# MainBoard.net
KiCad netlist of a schematic drawn in EAGLE
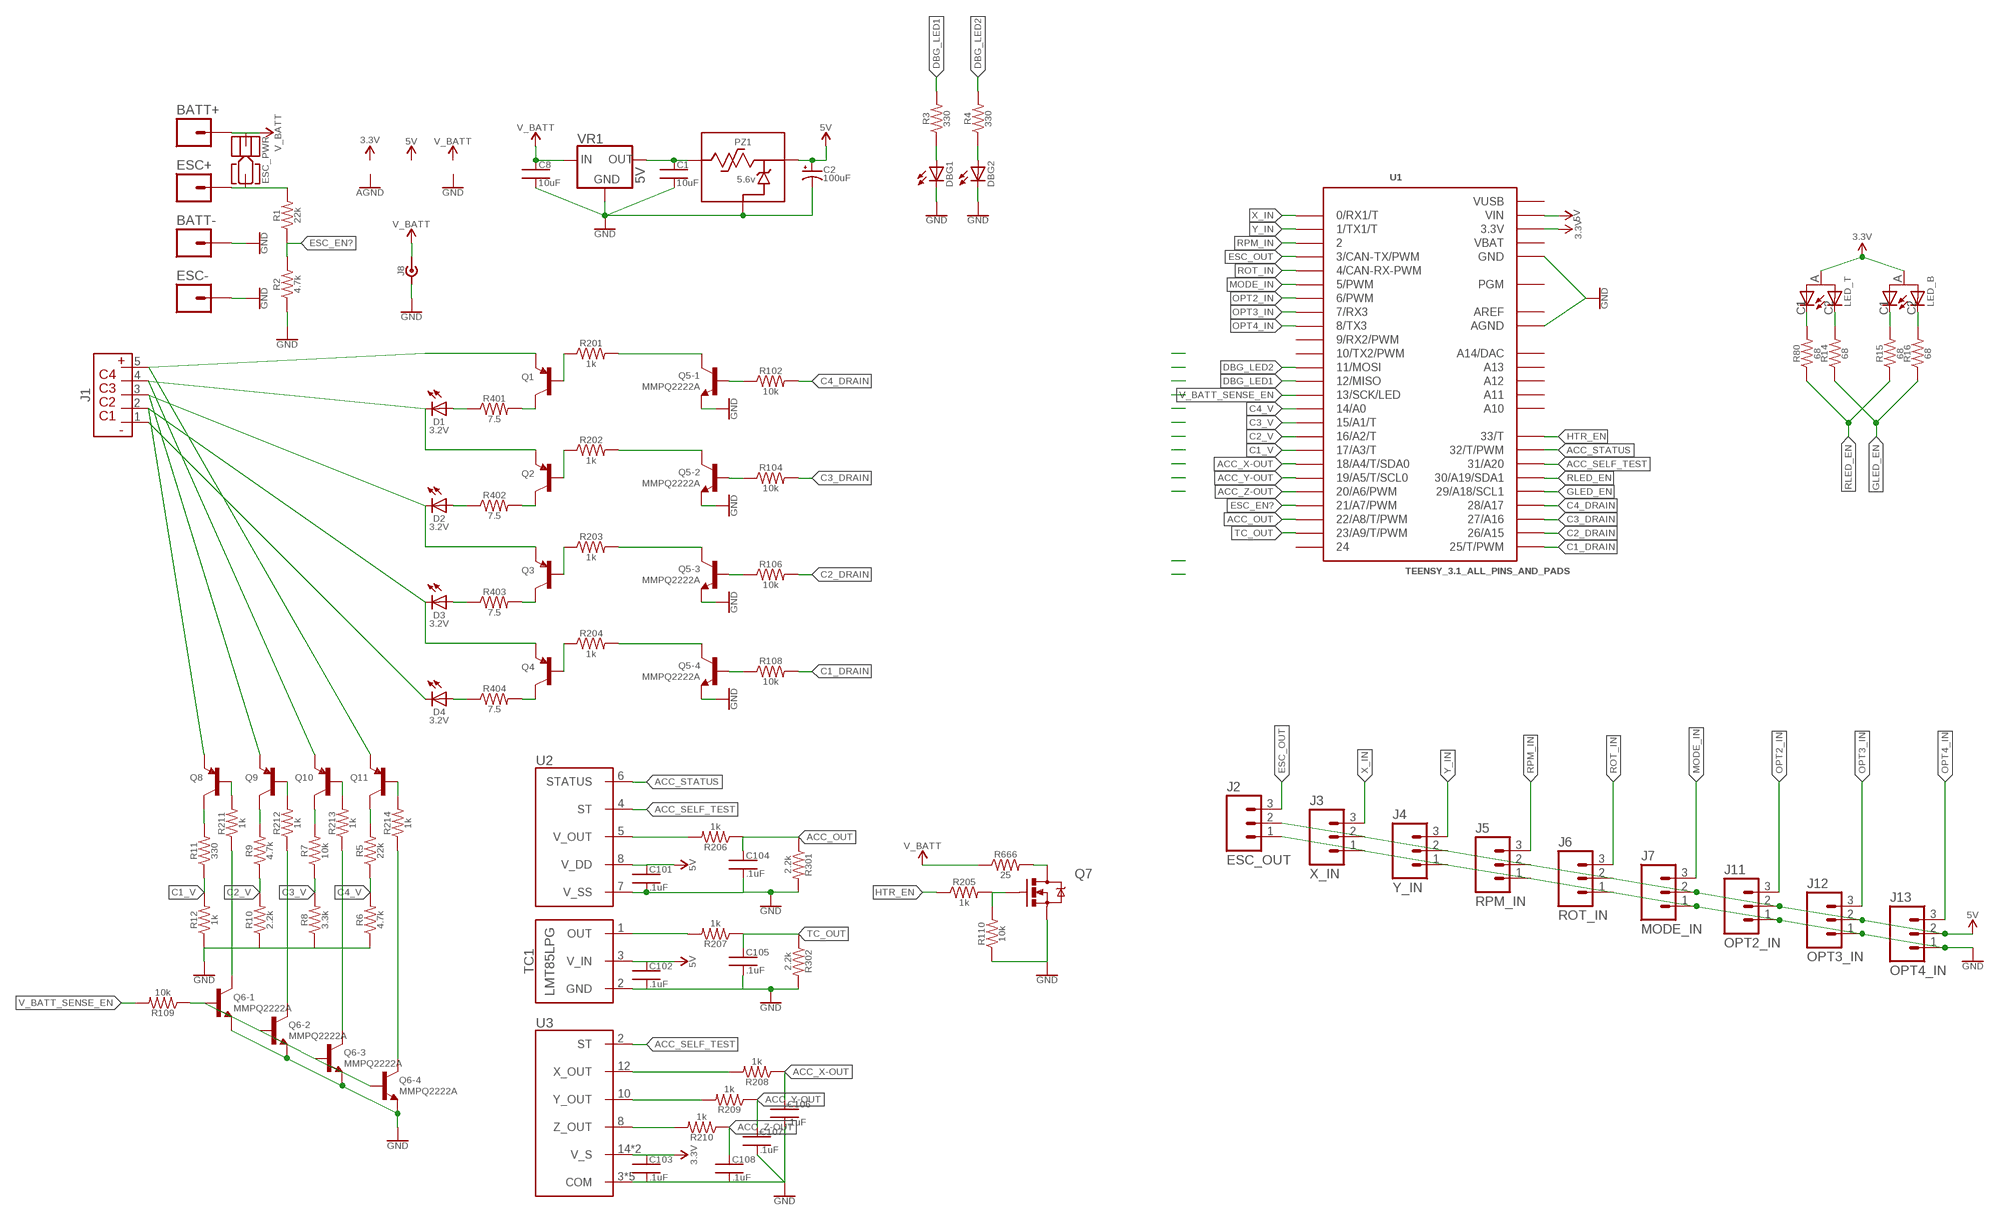
[diagram p0: schematic, sheet 1]

(export (version "E")
  (design (tool "Eeschema 10.0.6"))
  (components
    (comp (ref "BATT+")
      (value "14AWG")
      (footprint "eagle-import:14AWG_SMD")
      (libsource (lib "eagle-import") (part "14AWG"))
    )
    (comp (ref "BATT-")
      (value "14AWG")
      (footprint "eagle-import:14AWG_SMD")
      (libsource (lib "eagle-import") (part "14AWG"))
    )
    (comp (ref "C1")
      (value "10uF")
      (footprint "eagle-import:0805")
      (libsource (lib "eagle-import") (part "CAP_SMD"))
    )
    (comp (ref "C2")
      (value "100uF")
      (footprint "eagle-import:2917_D-CASE")
      (libsource (lib "eagle-import") (part "CAP_POL_SMD"))
    )
    (comp (ref "C8")
      (value "10uF")
      (footprint "eagle-import:0805")
      (libsource (lib "eagle-import") (part "CAP_SMD"))
    )
    (comp (ref "C101")
      (value ".1uF")
      (footprint "eagle-import:0805")
      (libsource (lib "eagle-import") (part "CAP_SMD"))
    )
    (comp (ref "C102")
      (value ".1uF")
      (footprint "eagle-import:0805")
      (libsource (lib "eagle-import") (part "CAP_SMD"))
    )
    (comp (ref "C103")
      (value ".1uF")
      (footprint "eagle-import:0805")
      (libsource (lib "eagle-import") (part "CAP_SMD"))
    )
    (comp (ref "C104")
      (value ".1uF")
      (footprint "eagle-import:0805")
      (libsource (lib "eagle-import") (part "CAP_SMD"))
    )
    (comp (ref "C105")
      (value ".1uF")
      (footprint "eagle-import:0805")
      (libsource (lib "eagle-import") (part "CAP_SMD"))
    )
    (comp (ref "C106")
      (value ".1uF")
      (footprint "eagle-import:0805")
      (libsource (lib "eagle-import") (part "CAP_SMD"))
    )
    (comp (ref "C107")
      (value ".1uF")
      (footprint "eagle-import:0805")
      (libsource (lib "eagle-import") (part "CAP_SMD"))
    )
    (comp (ref "C108")
      (value ".1uF")
      (footprint "eagle-import:0805")
      (libsource (lib "eagle-import") (part "CAP_SMD"))
    )
    (comp (ref "D1")
      (value "3.2V")
      (footprint "eagle-import:LED-2835")
      (libsource (lib "eagle-import") (part "LED2835"))
    )
    (comp (ref "D2")
      (value "3.2V")
      (footprint "eagle-import:LED-2835")
      (libsource (lib "eagle-import") (part "LED2835"))
    )
    (comp (ref "D3")
      (value "3.2V")
      (footprint "eagle-import:LED-2835")
      (libsource (lib "eagle-import") (part "LED2835"))
    )
    (comp (ref "D4")
      (value "3.2V")
      (footprint "eagle-import:LED-2835")
      (libsource (lib "eagle-import") (part "LED2835"))
    )
    (comp (ref "DBG1")
      (value "LED1206")
      (footprint "eagle-import:LED-1206")
      (libsource (lib "eagle-import") (part "LED1206"))
    )
    (comp (ref "DBG2")
      (value "LED1206")
      (footprint "eagle-import:LED-1206")
      (libsource (lib "eagle-import") (part "LED1206"))
    )
    (comp (ref "ESC+")
      (value "14AWG")
      (footprint "eagle-import:14AWG_SMD")
      (libsource (lib "eagle-import") (part "14AWG"))
    )
    (comp (ref "ESC-")
      (value "14AWG")
      (footprint "eagle-import:14AWG_SMD")
      (libsource (lib "eagle-import") (part "14AWG"))
    )
    (comp (ref "ESC_PWR")
      (value "JACK_PWR_SCREW")
      (footprint "eagle-import:JACK_PWR_SCREW")
      (libsource (lib "eagle-import") (part "JACK_PWR_SCREW"))
    )
    (comp (ref "J1")
      (value "BATT_BALANCER_PLUG_4S")
      (footprint "eagle-import:JST_MALE_5_PIN")
      (libsource (lib "eagle-import") (part "BATT_BALANCER_PLUG_4S"))
    )
    (comp (ref "J2")
      (value "ESC_OUT")
      (footprint "eagle-import:1X03")
      (libsource (lib "eagle-import") (part "M03"))
    )
    (comp (ref "J3")
      (value "X_IN")
      (footprint "eagle-import:1X03")
      (libsource (lib "eagle-import") (part "M03"))
    )
    (comp (ref "J4")
      (value "Y_IN")
      (footprint "eagle-import:1X03")
      (libsource (lib "eagle-import") (part "M03"))
    )
    (comp (ref "J5")
      (value "RPM_IN")
      (footprint "eagle-import:1X03")
      (libsource (lib "eagle-import") (part "M03"))
    )
    (comp (ref "J6")
      (value "ROT_IN")
      (footprint "eagle-import:1X03")
      (libsource (lib "eagle-import") (part "M03"))
    )
    (comp (ref "J7")
      (value "MODE_IN")
      (footprint "eagle-import:1X03")
      (libsource (lib "eagle-import") (part "M03"))
    )
    (comp (ref "J8")
      (value "PJ-082BH")
      (footprint "eagle-import:PJ-082BH")
      (libsource (lib "eagle-import") (part "PJ-082BH"))
    )
    (comp (ref "J11")
      (value "OPT2_IN")
      (footprint "eagle-import:1X03")
      (libsource (lib "eagle-import") (part "M03"))
    )
    (comp (ref "J12")
      (value "OPT3_IN")
      (footprint "eagle-import:1X03")
      (libsource (lib "eagle-import") (part "M03"))
    )
    (comp (ref "J13")
      (value "OPT4_IN")
      (footprint "eagle-import:1X03")
      (libsource (lib "eagle-import") (part "M03"))
    )
    (comp (ref "LED_B")
      (value "DIALIGHT_597-2751-607F")
      (footprint "eagle-import:DIALIGHT_1208_BI-COLOR")
      (libsource (lib "eagle-import") (part "DIALIGHT_597-2751-607F"))
    )
    (comp (ref "LED_T")
      (value "DIALIGHT_597-2751-607F")
      (footprint "eagle-import:DIALIGHT_1208_BI-COLOR")
      (libsource (lib "eagle-import") (part "DIALIGHT_597-2751-607F"))
    )
    (comp (ref "PZ1")
      (value "5.6v")
      (footprint "eagle-import:POLYZEN_LS")
      (libsource (lib "eagle-import") (part "POLYZEN_LS"))
    )
    (comp (ref "Q1")
      (value "BJT_PNP")
      (footprint "eagle-import:SOT23-3")
      (libsource (lib "eagle-import") (part "BJT_PNP"))
    )
    (comp (ref "Q2")
      (value "BJT_PNP")
      (footprint "eagle-import:SOT23-3")
      (libsource (lib "eagle-import") (part "BJT_PNP"))
    )
    (comp (ref "Q3")
      (value "BJT_PNP")
      (footprint "eagle-import:SOT23-3")
      (libsource (lib "eagle-import") (part "BJT_PNP"))
    )
    (comp (ref "Q4")
      (value "BJT_PNP")
      (footprint "eagle-import:SOT23-3")
      (libsource (lib "eagle-import") (part "BJT_PNP"))
    )
    (comp (ref "Q5")
      (value "MMPQ2222A")
      (footprint "eagle-import:SOIC_16")
      (libsource (lib "eagle-import") (part "MMPQ2222A"))
    )
    (comp (ref "Q6")
      (value "MMPQ2222A")
      (footprint "eagle-import:SOIC_16")
      (libsource (lib "eagle-import") (part "MMPQ2222A"))
    )
    (comp (ref "Q7")
      (value "MOSFET_N-CHANNEL_SOT23-3")
      (footprint "eagle-import:SOT23-3")
      (libsource (lib "eagle-import") (part "MOSFET_N-CHANNEL_SOT23-3"))
    )
    (comp (ref "Q8")
      (value "BJT_PNP")
      (footprint "eagle-import:SOT23-3")
      (libsource (lib "eagle-import") (part "BJT_PNP"))
    )
    (comp (ref "Q9")
      (value "BJT_PNP")
      (footprint "eagle-import:SOT23-3")
      (libsource (lib "eagle-import") (part "BJT_PNP"))
    )
    (comp (ref "Q10")
      (value "BJT_PNP")
      (footprint "eagle-import:SOT23-3")
      (libsource (lib "eagle-import") (part "BJT_PNP"))
    )
    (comp (ref "Q11")
      (value "BJT_PNP")
      (footprint "eagle-import:SOT23-3")
      (libsource (lib "eagle-import") (part "BJT_PNP"))
    )
    (comp (ref "R1")
      (value "22k")
      (footprint "eagle-import:0805")
      (libsource (lib "eagle-import") (part "RES_SMD0805"))
    )
    (comp (ref "R2")
      (value "4.7k")
      (footprint "eagle-import:0805")
      (libsource (lib "eagle-import") (part "RES_SMD0805"))
    )
    (comp (ref "R3")
      (value "330")
      (footprint "eagle-import:0805")
      (libsource (lib "eagle-import") (part "RES_SMD0805"))
    )
    (comp (ref "R4")
      (value "330")
      (footprint "eagle-import:0805")
      (libsource (lib "eagle-import") (part "RES_SMD0805"))
    )
    (comp (ref "R5")
      (value "22k")
      (footprint "eagle-import:0805")
      (libsource (lib "eagle-import") (part "RES_SMD0805"))
    )
    (comp (ref "R6")
      (value "4.7k")
      (footprint "eagle-import:0805")
      (libsource (lib "eagle-import") (part "RES_SMD0805"))
    )
    (comp (ref "R7")
      (value "10k")
      (footprint "eagle-import:0805")
      (libsource (lib "eagle-import") (part "RES_SMD0805"))
    )
    (comp (ref "R8")
      (value "3.3k")
      (footprint "eagle-import:0805")
      (libsource (lib "eagle-import") (part "RES_SMD0805"))
    )
    (comp (ref "R9")
      (value "4.7k")
      (footprint "eagle-import:0805")
      (libsource (lib "eagle-import") (part "RES_SMD0805"))
    )
    (comp (ref "R10")
      (value "2.2k")
      (footprint "eagle-import:0805")
      (libsource (lib "eagle-import") (part "RES_SMD0805"))
    )
    (comp (ref "R11")
      (value "330")
      (footprint "eagle-import:0805")
      (libsource (lib "eagle-import") (part "RES_SMD0805"))
    )
    (comp (ref "R12")
      (value "1k")
      (footprint "eagle-import:0805")
      (libsource (lib "eagle-import") (part "RES_SMD0805"))
    )
    (comp (ref "R14")
      (value "68")
      (footprint "eagle-import:0805")
      (libsource (lib "eagle-import") (part "RES_SMD0805"))
    )
    (comp (ref "R15")
      (value "68")
      (footprint "eagle-import:0805")
      (libsource (lib "eagle-import") (part "RES_SMD0805"))
    )
    (comp (ref "R16")
      (value "68")
      (footprint "eagle-import:0805")
      (libsource (lib "eagle-import") (part "RES_SMD0805"))
    )
    (comp (ref "R80")
      (value "68")
      (footprint "eagle-import:0805")
      (libsource (lib "eagle-import") (part "RES_SMD0805"))
    )
    (comp (ref "R102")
      (value "10k")
      (footprint "eagle-import:0805")
      (libsource (lib "eagle-import") (part "RES_SMD0805"))
    )
    (comp (ref "R104")
      (value "10k")
      (footprint "eagle-import:0805")
      (libsource (lib "eagle-import") (part "RES_SMD0805"))
    )
    (comp (ref "R106")
      (value "10k")
      (footprint "eagle-import:0805")
      (libsource (lib "eagle-import") (part "RES_SMD0805"))
    )
    (comp (ref "R108")
      (value "10k")
      (footprint "eagle-import:0805")
      (libsource (lib "eagle-import") (part "RES_SMD0805"))
    )
    (comp (ref "R109")
      (value "10k")
      (footprint "eagle-import:0805")
      (libsource (lib "eagle-import") (part "RES_SMD0805"))
    )
    (comp (ref "R110")
      (value "10k")
      (footprint "eagle-import:0805")
      (libsource (lib "eagle-import") (part "RES_SMD0805"))
    )
    (comp (ref "R201")
      (value "1k")
      (footprint "eagle-import:0805")
      (libsource (lib "eagle-import") (part "RES_SMD0805"))
    )
    (comp (ref "R202")
      (value "1k")
      (footprint "eagle-import:0805")
      (libsource (lib "eagle-import") (part "RES_SMD0805"))
    )
    (comp (ref "R203")
      (value "1k")
      (footprint "eagle-import:0805")
      (libsource (lib "eagle-import") (part "RES_SMD0805"))
    )
    (comp (ref "R204")
      (value "1k")
      (footprint "eagle-import:0805")
      (libsource (lib "eagle-import") (part "RES_SMD0805"))
    )
    (comp (ref "R205")
      (value "1k")
      (footprint "eagle-import:0805")
      (libsource (lib "eagle-import") (part "RES_SMD0805"))
    )
    (comp (ref "R206")
      (value "1k")
      (footprint "eagle-import:0805")
      (libsource (lib "eagle-import") (part "RES_SMD0805"))
    )
    (comp (ref "R207")
      (value "1k")
      (footprint "eagle-import:0805")
      (libsource (lib "eagle-import") (part "RES_SMD0805"))
    )
    (comp (ref "R208")
      (value "1k")
      (footprint "eagle-import:0805")
      (libsource (lib "eagle-import") (part "RES_SMD0805"))
    )
    (comp (ref "R209")
      (value "1k")
      (footprint "eagle-import:0805")
      (libsource (lib "eagle-import") (part "RES_SMD0805"))
    )
    (comp (ref "R210")
      (value "1k")
      (footprint "eagle-import:0805")
      (libsource (lib "eagle-import") (part "RES_SMD0805"))
    )
    (comp (ref "R211")
      (value "1k")
      (footprint "eagle-import:0805")
      (libsource (lib "eagle-import") (part "RES_SMD0805"))
    )
    (comp (ref "R212")
      (value "1k")
      (footprint "eagle-import:0805")
      (libsource (lib "eagle-import") (part "RES_SMD0805"))
    )
    (comp (ref "R213")
      (value "1k")
      (footprint "eagle-import:0805")
      (libsource (lib "eagle-import") (part "RES_SMD0805"))
    )
    (comp (ref "R214")
      (value "1k")
      (footprint "eagle-import:0805")
      (libsource (lib "eagle-import") (part "RES_SMD0805"))
    )
    (comp (ref "R301")
      (value "2.2k")
      (footprint "eagle-import:0805")
      (libsource (lib "eagle-import") (part "RES_SMD0805"))
    )
    (comp (ref "R302")
      (value "2.2k")
      (footprint "eagle-import:0805")
      (libsource (lib "eagle-import") (part "RES_SMD0805"))
    )
    (comp (ref "R401")
      (value "7.5")
      (footprint "eagle-import:1206")
      (libsource (lib "eagle-import") (part "RES_SMD1206"))
    )
    (comp (ref "R402")
      (value "7.5")
      (footprint "eagle-import:1206")
      (libsource (lib "eagle-import") (part "RES_SMD1206"))
    )
    (comp (ref "R403")
      (value "7.5")
      (footprint "eagle-import:1206")
      (libsource (lib "eagle-import") (part "RES_SMD1206"))
    )
    (comp (ref "R404")
      (value "7.5")
      (footprint "eagle-import:1206")
      (libsource (lib "eagle-import") (part "RES_SMD1206"))
    )
    (comp (ref "R666")
      (value "25")
      (footprint "eagle-import:TO-220-R")
      (libsource (lib "eagle-import") (part "AP851"))
    )
    (comp (ref "TC1")
      (value "LMT85LPG")
      (footprint "eagle-import:TO-92")
      (libsource (lib "eagle-import") (part "LMT85LPG"))
    )
    (comp (ref "U1")
      (value "TEENSY_3.1_ALL_PINS_AND_PADS")
      (footprint "eagle-import:TEENSY_3.1_ALLPINS")
      (libsource (lib "eagle-import") (part "TEENSY_3.1_ALL_PINS_AND_PADS"))
    )
    (comp (ref "U2")
      (value "MMA1211KEG")
      (footprint "eagle-import:SOIC_16_WIDE")
      (libsource (lib "eagle-import") (part "MMA1211KEG"))
    )
    (comp (ref "U3")
      (value "ADXL326")
      (footprint "eagle-import:LFCSP_LQ")
      (libsource (lib "eagle-import") (part "ADXL326"))
    )
    (comp (ref "VR1")
      (value "5V")
      (footprint "eagle-import:TSR_2-XXXX")
      (libsource (lib "eagle-import") (part "TSR_2-XXXX"))
    )
  )
  (nets
    (net (code "1") (name "/AREF") (class "Default")
      (node (ref "U1") (pin "AREF") (pinfunction "AREF_AREF") (pintype "power_in"))
    )
    (net (code "2") (name "/VBAT") (class "Default")
      (node (ref "U1") (pin "VBAT") (pinfunction "VBAT_VBAT") (pintype "power_in"))
    )
    (net (code "3") (name "/VUSB") (class "Default")
      (node (ref "U1") (pin "VUSB") (pinfunction "VUSB_VUSB") (pintype "power_in"))
    )
    (net (code "4") (name "3.3V") (class "Default")
      (node (ref "C103") (pin "1") (pinfunction "1_1") (pintype "passive"))
      (node (ref "LED_B") (pin "A") (pinfunction "A_A") (pintype "passive"))
      (node (ref "LED_T") (pin "A") (pinfunction "A_A") (pintype "passive"))
      (node (ref "U1") (pin "3.3V") (pinfunction "3.3V_3.3V") (pintype "power_in"))
      (node (ref "U1") (pin "3.3V1") (pinfunction "3.3V_3.3V1") (pintype "power_in"))
      (node (ref "U1") (pin "3.3V2") (pinfunction "3.3V_3.3V2") (pintype "power_in"))
      (node (ref "U3") (pin "14") (pinfunction "V_S_14") (pintype "bidirectional"))
      (node (ref "U3") (pin "15") (pinfunction "V_S_15") (pintype "bidirectional"))
    )
    (net (code "5") (name "5V") (class "Default")
      (node (ref "C101") (pin "1") (pinfunction "1_1") (pintype "passive"))
      (node (ref "C102") (pin "1") (pinfunction "1_1") (pintype "passive"))
      (node (ref "C2") (pin "A+") (pinfunction "+_A+") (pintype "passive"))
      (node (ref "J11") (pin "2") (pinfunction "2_2") (pintype "passive"))
      (node (ref "J12") (pin "2") (pinfunction "2_2") (pintype "passive"))
      (node (ref "J13") (pin "2") (pinfunction "2_2") (pintype "passive"))
      (node (ref "J2") (pin "2") (pinfunction "2_2") (pintype "passive"))
      (node (ref "J3") (pin "2") (pinfunction "2_2") (pintype "passive"))
      (node (ref "J4") (pin "2") (pinfunction "2_2") (pintype "passive"))
      (node (ref "J5") (pin "2") (pinfunction "2_2") (pintype "passive"))
      (node (ref "J6") (pin "2") (pinfunction "2_2") (pintype "passive"))
      (node (ref "J7") (pin "2") (pinfunction "2_2") (pintype "passive"))
      (node (ref "PZ1") (pin "VOUT") (pinfunction "V_OUT_VOUT") (pintype "bidirectional"))
      (node (ref "TC1") (pin "3") (pinfunction "V_IN_3") (pintype "bidirectional"))
      (node (ref "U1") (pin "VIN") (pinfunction "VIN_VIN") (pintype "power_in"))
      (node (ref "U2") (pin "8") (pinfunction "V_DD_8") (pintype "bidirectional"))
    )
    (net (code "6") (name "ACC_OUT") (class "Default")
      (node (ref "C104") (pin "1") (pinfunction "1_1") (pintype "passive"))
      (node (ref "R206") (pin "1") (pinfunction "1_1") (pintype "passive"))
      (node (ref "R301") (pin "1") (pinfunction "1_1") (pintype "passive"))
      (node (ref "U1") (pin "22/A8") (pinfunction "22/A8/T/PWM_22/A8") (pintype "bidirectional"))
    )
    (net (code "7") (name "ACC_SELF_TEST") (class "Default")
      (node (ref "U1") (pin "31") (pinfunction "31/A20_31") (pintype "bidirectional"))
      (node (ref "U2") (pin "4") (pinfunction "ST_4") (pintype "bidirectional"))
      (node (ref "U3") (pin "2") (pinfunction "ST_2") (pintype "bidirectional"))
    )
    (net (code "8") (name "ACC_STATUS") (class "Default")
      (node (ref "U1") (pin "32") (pinfunction "32/T/PWM_32") (pintype "bidirectional"))
      (node (ref "U2") (pin "6") (pinfunction "STATUS_6") (pintype "bidirectional"))
    )
    (net (code "9") (name "ACC_X-OUT") (class "Default")
      (node (ref "C106") (pin "1") (pinfunction "1_1") (pintype "passive"))
      (node (ref "R208") (pin "1") (pinfunction "1_1") (pintype "passive"))
      (node (ref "U1") (pin "18/A4") (pinfunction "18/A4/T/SDA0_18/A4") (pintype "bidirectional"))
    )
    (net (code "10") (name "ACC_Y-OUT") (class "Default")
      (node (ref "C107") (pin "1") (pinfunction "1_1") (pintype "passive"))
      (node (ref "R209") (pin "1") (pinfunction "1_1") (pintype "passive"))
      (node (ref "U1") (pin "19/A5") (pinfunction "19/A5/T/SCL0_19/A5") (pintype "bidirectional"))
    )
    (net (code "11") (name "ACC_Z-OUT") (class "Default")
      (node (ref "C108") (pin "1") (pinfunction "1_1") (pintype "passive"))
      (node (ref "R210") (pin "1") (pinfunction "1_1") (pintype "passive"))
      (node (ref "U1") (pin "20/A6") (pinfunction "20/A6/PWM_20/A6") (pintype "bidirectional"))
    )
    (net (code "13") (name "C1_DRAIN") (class "Default")
      (node (ref "R108") (pin "2") (pinfunction "2_2") (pintype "passive"))
      (node (ref "U1") (pin "25") (pinfunction "25/T/PWM_25") (pintype "bidirectional"))
    )
    (net (code "14") (name "C1_V") (class "Default")
      (node (ref "R11") (pin "1") (pinfunction "1_1") (pintype "passive"))
      (node (ref "R12") (pin "2") (pinfunction "2_2") (pintype "passive"))
      (node (ref "U1") (pin "17/A3") (pinfunction "17/A3/T_17/A3") (pintype "bidirectional"))
    )
    (net (code "15") (name "C2_DRAIN") (class "Default")
      (node (ref "R106") (pin "2") (pinfunction "2_2") (pintype "passive"))
      (node (ref "U1") (pin "26") (pinfunction "26/A15_26") (pintype "bidirectional"))
    )
    (net (code "16") (name "C2_V") (class "Default")
      (node (ref "R10") (pin "2") (pinfunction "2_2") (pintype "passive"))
      (node (ref "R9") (pin "1") (pinfunction "1_1") (pintype "passive"))
      (node (ref "U1") (pin "16/A2") (pinfunction "16/A2/T_16/A2") (pintype "bidirectional"))
    )
    (net (code "17") (name "C3_DRAIN") (class "Default")
      (node (ref "R104") (pin "2") (pinfunction "2_2") (pintype "passive"))
      (node (ref "U1") (pin "27") (pinfunction "27/A16_27") (pintype "bidirectional"))
    )
    (net (code "18") (name "C3_V") (class "Default")
      (node (ref "R7") (pin "1") (pinfunction "1_1") (pintype "passive"))
      (node (ref "R8") (pin "2") (pinfunction "2_2") (pintype "passive"))
      (node (ref "U1") (pin "15/A1") (pinfunction "15/A1/T_15/A1") (pintype "bidirectional"))
    )
    (net (code "19") (name "C4_DRAIN") (class "Default")
      (node (ref "R102") (pin "2") (pinfunction "2_2") (pintype "passive"))
      (node (ref "U1") (pin "28") (pinfunction "28/A17_28") (pintype "bidirectional"))
    )
    (net (code "20") (name "C4_V") (class "Default")
      (node (ref "R5") (pin "1") (pinfunction "1_1") (pintype "passive"))
      (node (ref "R6") (pin "2") (pinfunction "2_2") (pintype "passive"))
      (node (ref "U1") (pin "14/A0") (pinfunction "14/A0_14/A0") (pintype "bidirectional"))
    )
    (net (code "21") (name "DBG_LED1") (class "Default")
      (node (ref "R3") (pin "2") (pinfunction "2_2") (pintype "passive"))
      (node (ref "U1") (pin "12") (pinfunction "12/MISO_12") (pintype "bidirectional"))
    )
    (net (code "22") (name "DBG_LED2") (class "Default")
      (node (ref "R4") (pin "2") (pinfunction "2_2") (pintype "passive"))
      (node (ref "U1") (pin "11") (pinfunction "11/MOSI_11") (pintype "bidirectional"))
    )
    (net (code "23") (name "ESC_EN?") (class "Default")
      (node (ref "R1") (pin "1") (pinfunction "1_1") (pintype "passive"))
      (node (ref "R2") (pin "2") (pinfunction "2_2") (pintype "passive"))
      (node (ref "U1") (pin "21/A7") (pinfunction "21/A7/PWM_21/A7") (pintype "bidirectional"))
    )
    (net (code "24") (name "ESC_OUT") (class "Default")
      (node (ref "J2") (pin "3") (pinfunction "3_3") (pintype "passive"))
      (node (ref "U1") (pin "3") (pinfunction "3/CAN-TX/PWM_3") (pintype "bidirectional"))
    )
    (net (code "25") (name "GLED_EN") (class "Default")
      (node (ref "R14") (pin "1") (pinfunction "1_1") (pintype "passive"))
      (node (ref "R16") (pin "1") (pinfunction "1_1") (pintype "passive"))
      (node (ref "U1") (pin "29") (pinfunction "29/A18/SCL1_29") (pintype "bidirectional"))
    )
    (net (code "26") (name "GND") (class "Default")
      (node (ref "BATT-") (pin "P") (pinfunction "1_P") (pintype "passive"))
      (node (ref "C1") (pin "2") (pinfunction "2_2") (pintype "passive"))
      (node (ref "C101") (pin "2") (pinfunction "2_2") (pintype "passive"))
      (node (ref "C102") (pin "2") (pinfunction "2_2") (pintype "passive"))
      (node (ref "C103") (pin "2") (pinfunction "2_2") (pintype "passive"))
      (node (ref "C104") (pin "2") (pinfunction "2_2") (pintype "passive"))
      (node (ref "C105") (pin "2") (pinfunction "2_2") (pintype "passive"))
      (node (ref "C106") (pin "2") (pinfunction "2_2") (pintype "passive"))
      (node (ref "C107") (pin "2") (pinfunction "2_2") (pintype "passive"))
      (node (ref "C108") (pin "2") (pinfunction "2_2") (pintype "passive"))
      (node (ref "C2") (pin "C-") (pinfunction "-_C-") (pintype "passive"))
      (node (ref "C8") (pin "2") (pinfunction "2_2") (pintype "passive"))
      (node (ref "DBG1") (pin "C") (pinfunction "C_C") (pintype "passive"))
      (node (ref "DBG2") (pin "C") (pinfunction "C_C") (pintype "passive"))
      (node (ref "ESC-") (pin "P") (pinfunction "1_P") (pintype "passive"))
      (node (ref "J11") (pin "1") (pinfunction "1_1") (pintype "passive"))
      (node (ref "J12") (pin "1") (pinfunction "1_1") (pintype "passive"))
      (node (ref "J13") (pin "1") (pinfunction "1_1") (pintype "passive"))
      (node (ref "J2") (pin "1") (pinfunction "1_1") (pintype "passive"))
      (node (ref "J3") (pin "1") (pinfunction "1_1") (pintype "passive"))
      (node (ref "J4") (pin "1") (pinfunction "1_1") (pintype "passive"))
      (node (ref "J5") (pin "1") (pinfunction "1_1") (pintype "passive"))
      (node (ref "J6") (pin "1") (pinfunction "1_1") (pintype "passive"))
      (node (ref "J7") (pin "1") (pinfunction "1_1") (pintype "passive"))
      (node (ref "J8") (pin "2") (pinfunction "2_2") (pintype "bidirectional"))
      (node (ref "J8") (pin "SH1") (pinfunction "2_SH1") (pintype "bidirectional"))
      (node (ref "J8") (pin "SH2") (pinfunction "2_SH2") (pintype "bidirectional"))
      (node (ref "J8") (pin "SH3") (pinfunction "2_SH3") (pintype "bidirectional"))
      (node (ref "J8") (pin "SH4") (pinfunction "2_SH4") (pintype "bidirectional"))
      (node (ref "PZ1") (pin "GND") (pinfunction "GND_GND") (pintype "bidirectional"))
      (node (ref "Q5") (pin "10") (pinfunction "E_10") (pintype "passive"))
      (node (ref "Q5") (pin "12") (pinfunction "E_12") (pintype "passive"))
      (node (ref "Q5") (pin "14") (pinfunction "E_14") (pintype "passive"))
      (node (ref "Q5") (pin "16") (pinfunction "E_16") (pintype "passive"))
      (node (ref "Q6") (pin "10") (pinfunction "E_10") (pintype "passive"))
      (node (ref "Q6") (pin "12") (pinfunction "E_12") (pintype "passive"))
      (node (ref "Q6") (pin "14") (pinfunction "E_14") (pintype "passive"))
      (node (ref "Q6") (pin "16") (pinfunction "E_16") (pintype "passive"))
      (node (ref "Q7") (pin "2") (pinfunction "S_2") (pintype "passive"))
      (node (ref "R10") (pin "1") (pinfunction "1_1") (pintype "passive"))
      (node (ref "R110") (pin "1") (pinfunction "1_1") (pintype "passive"))
      (node (ref "R12") (pin "1") (pinfunction "1_1") (pintype "passive"))
      (node (ref "R2") (pin "1") (pinfunction "1_1") (pintype "passive"))
      (node (ref "R301") (pin "2") (pinfunction "2_2") (pintype "passive"))
      (node (ref "R302") (pin "2") (pinfunction "2_2") (pintype "passive"))
      (node (ref "R6") (pin "1") (pinfunction "1_1") (pintype "passive"))
      (node (ref "R8") (pin "1") (pinfunction "1_1") (pintype "passive"))
      (node (ref "TC1") (pin "2") (pinfunction "GND_2") (pintype "bidirectional"))
      (node (ref "U1") (pin "AGND") (pinfunction "AGND_AGND") (pintype "power_in"))
      (node (ref "U1") (pin "GND") (pinfunction "GND_GND") (pintype "power_in"))
      (node (ref "U1") (pin "GND1") (pinfunction "GND_GND1") (pintype "power_in"))
      (node (ref "U1") (pin "GND2") (pinfunction "GND_GND2") (pintype "power_in"))
      (node (ref "U2") (pin "7") (pinfunction "V_SS_7") (pintype "bidirectional"))
      (node (ref "U3") (pin "17") (pinfunction "COM_17") (pintype "bidirectional"))
      (node (ref "U3") (pin "3") (pinfunction "COM_3") (pintype "bidirectional"))
      (node (ref "U3") (pin "5") (pinfunction "COM_5") (pintype "bidirectional"))
      (node (ref "U3") (pin "6") (pinfunction "COM_6") (pintype "bidirectional"))
      (node (ref "U3") (pin "7") (pinfunction "COM_7") (pintype "bidirectional"))
      (node (ref "VR1") (pin "2") (pinfunction "GND_2") (pintype "input"))
    )
    (net (code "27") (name "HTR_EN") (class "Default")
      (node (ref "R205") (pin "1") (pinfunction "1_1") (pintype "passive"))
      (node (ref "U1") (pin "33") (pinfunction "33/T_33") (pintype "bidirectional"))
    )
    (net (code "28") (name "MODE_IN") (class "Default")
      (node (ref "J7") (pin "3") (pinfunction "3_3") (pintype "passive"))
      (node (ref "U1") (pin "5") (pinfunction "5/PWM_5") (pintype "bidirectional"))
    )
    (net (code "29") (name "Net-(D1-PadA)") (class "Default")
      (node (ref "D1") (pin "A") (pinfunction "A_A") (pintype "passive"))
      (node (ref "R401") (pin "1") (pinfunction "1_1") (pintype "passive"))
    )
    (net (code "30") (name "Net-(D2-PadA)") (class "Default")
      (node (ref "D2") (pin "A") (pinfunction "A_A") (pintype "passive"))
      (node (ref "R402") (pin "1") (pinfunction "1_1") (pintype "passive"))
    )
    (net (code "31") (name "Net-(D3-PadA)") (class "Default")
      (node (ref "D3") (pin "A") (pinfunction "A_A") (pintype "passive"))
      (node (ref "R403") (pin "1") (pinfunction "1_1") (pintype "passive"))
    )
    (net (code "32") (name "Net-(D4-PadA)") (class "Default")
      (node (ref "D4") (pin "A") (pinfunction "A_A") (pintype "passive"))
      (node (ref "R404") (pin "1") (pinfunction "1_1") (pintype "passive"))
    )
    (net (code "33") (name "Net-(DBG1-PadA)") (class "Default")
      (node (ref "DBG1") (pin "A") (pinfunction "A_A") (pintype "passive"))
      (node (ref "R3") (pin "1") (pinfunction "1_1") (pintype "passive"))
    )
    (net (code "34") (name "Net-(DBG2-PadA)") (class "Default")
      (node (ref "DBG2") (pin "A") (pinfunction "A_A") (pintype "passive"))
      (node (ref "R4") (pin "1") (pinfunction "1_1") (pintype "passive"))
    )
    (net (code "35") (name "Net-(ESC+-1)") (class "Default")
      (node (ref "ESC+") (pin "P") (pinfunction "1_P") (pintype "passive"))
      (node (ref "ESC_PWR") (pin "1") (pinfunction "1_1") (pintype "bidirectional"))
      (node (ref "R1") (pin "2") (pinfunction "2_2") (pintype "passive"))
    )
    (net (code "36") (name "Net-(J1-C1)") (class "Default")
      (node (ref "D3") (pin "C") (pinfunction "C_C") (pintype "passive"))
      (node (ref "J1") (pin "2") (pinfunction "C1_2") (pintype "bidirectional"))
      (node (ref "Q4") (pin "2") (pinfunction "E_2") (pintype "passive"))
      (node (ref "Q8") (pin "2") (pinfunction "E_2") (pintype "passive"))
    )
    (net (code "37") (name "Net-(J1-C2)") (class "Default")
      (node (ref "D2") (pin "C") (pinfunction "C_C") (pintype "passive"))
      (node (ref "J1") (pin "3") (pinfunction "C2_3") (pintype "bidirectional"))
      (node (ref "Q3") (pin "2") (pinfunction "E_2") (pintype "passive"))
      (node (ref "Q9") (pin "2") (pinfunction "E_2") (pintype "passive"))
    )
    (net (code "38") (name "Net-(J1-C3)") (class "Default")
      (node (ref "D1") (pin "C") (pinfunction "C_C") (pintype "passive"))
      (node (ref "J1") (pin "4") (pinfunction "C3_4") (pintype "bidirectional"))
      (node (ref "Q10") (pin "2") (pinfunction "E_2") (pintype "passive"))
      (node (ref "Q2") (pin "2") (pinfunction "E_2") (pintype "passive"))
    )
    (net (code "39") (name "Net-(J1-C4)") (class "Default")
      (node (ref "J1") (pin "5") (pinfunction "C4_5") (pintype "bidirectional"))
      (node (ref "Q1") (pin "2") (pinfunction "E_2") (pintype "passive"))
      (node (ref "Q11") (pin "2") (pinfunction "E_2") (pintype "passive"))
    )
    (net (code "40") (name "Net-(J1-V0)") (class "Default")
      (node (ref "D4") (pin "C") (pinfunction "C_C") (pintype "passive"))
      (node (ref "J1") (pin "1") (pinfunction "V0_1") (pintype "bidirectional"))
    )
    (net (code "41") (name "Net-(LED_B-PadC1)") (class "Default")
      (node (ref "LED_B") (pin "C1") (pinfunction "C1_C1") (pintype "passive"))
      (node (ref "R15") (pin "2") (pinfunction "2_2") (pintype "passive"))
    )
    (net (code "42") (name "Net-(LED_B-PadC2)") (class "Default")
      (node (ref "LED_B") (pin "C2") (pinfunction "C2_C2") (pintype "passive"))
      (node (ref "R16") (pin "2") (pinfunction "2_2") (pintype "passive"))
    )
    (net (code "43") (name "Net-(LED_T-PadC1)") (class "Default")
      (node (ref "LED_T") (pin "C1") (pinfunction "C1_C1") (pintype "passive"))
      (node (ref "R80") (pin "2") (pinfunction "2_2") (pintype "passive"))
    )
    (net (code "44") (name "Net-(LED_T-PadC2)") (class "Default")
      (node (ref "LED_T") (pin "C2") (pinfunction "C2_C2") (pintype "passive"))
      (node (ref "R14") (pin "2") (pinfunction "2_2") (pintype "passive"))
    )
    (net (code "45") (name "Net-(PZ1-V_IN)") (class "Default")
      (node (ref "C1") (pin "1") (pinfunction "1_1") (pintype "passive"))
      (node (ref "PZ1") (pin "VIN") (pinfunction "V_IN_VIN") (pintype "bidirectional"))
      (node (ref "VR1") (pin "3") (pinfunction "OUT_3") (pintype "passive"))
    )
    (net (code "46") (name "Net-(Q1-B)") (class "Default")
      (node (ref "Q1") (pin "1") (pinfunction "B_1") (pintype "passive"))
      (node (ref "R201") (pin "1") (pinfunction "1_1") (pintype "passive"))
    )
    (net (code "47") (name "Net-(Q1-C)") (class "Default")
      (node (ref "Q1") (pin "3") (pinfunction "C_3") (pintype "passive"))
      (node (ref "R401") (pin "2") (pinfunction "2_2") (pintype "passive"))
    )
    (net (code "48") (name "Net-(Q2-B)") (class "Default")
      (node (ref "Q2") (pin "1") (pinfunction "B_1") (pintype "passive"))
      (node (ref "R202") (pin "1") (pinfunction "1_1") (pintype "passive"))
    )
    (net (code "49") (name "Net-(Q2-C)") (class "Default")
      (node (ref "Q2") (pin "3") (pinfunction "C_3") (pintype "passive"))
      (node (ref "R402") (pin "2") (pinfunction "2_2") (pintype "passive"))
    )
    (net (code "50") (name "Net-(Q3-B)") (class "Default")
      (node (ref "Q3") (pin "1") (pinfunction "B_1") (pintype "passive"))
      (node (ref "R203") (pin "1") (pinfunction "1_1") (pintype "passive"))
    )
    (net (code "51") (name "Net-(Q3-C)") (class "Default")
      (node (ref "Q3") (pin "3") (pinfunction "C_3") (pintype "passive"))
      (node (ref "R403") (pin "2") (pinfunction "2_2") (pintype "passive"))
    )
    (net (code "52") (name "Net-(Q4-B)") (class "Default")
      (node (ref "Q4") (pin "1") (pinfunction "B_1") (pintype "passive"))
      (node (ref "R204") (pin "1") (pinfunction "1_1") (pintype "passive"))
    )
    (net (code "53") (name "Net-(Q4-C)") (class "Default")
      (node (ref "Q4") (pin "3") (pinfunction "C_3") (pintype "passive"))
      (node (ref "R404") (pin "2") (pinfunction "2_2") (pintype "passive"))
    )
    (net (code "54") (name "Net-(Q5A-B)") (class "Default")
      (node (ref "Q5") (pin "15") (pinfunction "B_15") (pintype "passive"))
      (node (ref "R102") (pin "1") (pinfunction "1_1") (pintype "passive"))
    )
    (net (code "55") (name "Net-(Q5A-C-Pad1)") (class "Default")
      (node (ref "Q5") (pin "1") (pinfunction "C_1") (pintype "passive"))
      (node (ref "Q5") (pin "2") (pinfunction "C_2") (pintype "passive"))
      (node (ref "R201") (pin "2") (pinfunction "2_2") (pintype "passive"))
    )
    (net (code "56") (name "Net-(Q5B-B)") (class "Default")
      (node (ref "Q5") (pin "13") (pinfunction "B_13") (pintype "passive"))
      (node (ref "R104") (pin "1") (pinfunction "1_1") (pintype "passive"))
    )
    (net (code "57") (name "Net-(Q5B-C-Pad3)") (class "Default")
      (node (ref "Q5") (pin "3") (pinfunction "C_3") (pintype "passive"))
      (node (ref "Q5") (pin "4") (pinfunction "C_4") (pintype "passive"))
      (node (ref "R202") (pin "2") (pinfunction "2_2") (pintype "passive"))
    )
    (net (code "58") (name "Net-(Q5C-B)") (class "Default")
      (node (ref "Q5") (pin "11") (pinfunction "B_11") (pintype "passive"))
      (node (ref "R106") (pin "1") (pinfunction "1_1") (pintype "passive"))
    )
    (net (code "59") (name "Net-(Q5C-C-Pad5)") (class "Default")
      (node (ref "Q5") (pin "5") (pinfunction "C_5") (pintype "passive"))
      (node (ref "Q5") (pin "6") (pinfunction "C_6") (pintype "passive"))
      (node (ref "R203") (pin "2") (pinfunction "2_2") (pintype "passive"))
    )
    (net (code "60") (name "Net-(Q5D-B)") (class "Default")
      (node (ref "Q5") (pin "9") (pinfunction "B_9") (pintype "passive"))
      (node (ref "R108") (pin "1") (pinfunction "1_1") (pintype "passive"))
    )
    (net (code "61") (name "Net-(Q5D-C-Pad7)") (class "Default")
      (node (ref "Q5") (pin "7") (pinfunction "C_7") (pintype "passive"))
      (node (ref "Q5") (pin "8") (pinfunction "C_8") (pintype "passive"))
      (node (ref "R204") (pin "2") (pinfunction "2_2") (pintype "passive"))
    )
    (net (code "62") (name "Net-(Q6A-B)") (class "Default")
      (node (ref "Q6") (pin "11") (pinfunction "B_11") (pintype "passive"))
      (node (ref "Q6") (pin "13") (pinfunction "B_13") (pintype "passive"))
      (node (ref "Q6") (pin "15") (pinfunction "B_15") (pintype "passive"))
      (node (ref "Q6") (pin "9") (pinfunction "B_9") (pintype "passive"))
      (node (ref "R109") (pin "1") (pinfunction "1_1") (pintype "passive"))
    )
    (net (code "63") (name "Net-(Q6A-C-Pad1)") (class "Default")
      (node (ref "Q6") (pin "1") (pinfunction "C_1") (pintype "passive"))
      (node (ref "Q6") (pin "2") (pinfunction "C_2") (pintype "passive"))
      (node (ref "R211") (pin "1") (pinfunction "1_1") (pintype "passive"))
    )
    (net (code "64") (name "Net-(Q6B-C-Pad3)") (class "Default")
      (node (ref "Q6") (pin "3") (pinfunction "C_3") (pintype "passive"))
      (node (ref "Q6") (pin "4") (pinfunction "C_4") (pintype "passive"))
      (node (ref "R212") (pin "1") (pinfunction "1_1") (pintype "passive"))
    )
    (net (code "65") (name "Net-(Q6C-C-Pad5)") (class "Default")
      (node (ref "Q6") (pin "5") (pinfunction "C_5") (pintype "passive"))
      (node (ref "Q6") (pin "6") (pinfunction "C_6") (pintype "passive"))
      (node (ref "R213") (pin "1") (pinfunction "1_1") (pintype "passive"))
    )
    (net (code "66") (name "Net-(Q6D-C-Pad7)") (class "Default")
      (node (ref "Q6") (pin "7") (pinfunction "C_7") (pintype "passive"))
      (node (ref "Q6") (pin "8") (pinfunction "C_8") (pintype "passive"))
      (node (ref "R214") (pin "1") (pinfunction "1_1") (pintype "passive"))
    )
    (net (code "67") (name "Net-(Q7-D)") (class "Default")
      (node (ref "Q7") (pin "3") (pinfunction "D_3") (pintype "passive"))
      (node (ref "R666") (pin "2") (pinfunction "2_2") (pintype "passive"))
    )
    (net (code "68") (name "Net-(Q7-G)") (class "Default")
      (node (ref "Q7") (pin "1") (pinfunction "G_1") (pintype "passive"))
      (node (ref "R110") (pin "2") (pinfunction "2_2") (pintype "passive"))
      (node (ref "R205") (pin "2") (pinfunction "2_2") (pintype "passive"))
    )
    (net (code "69") (name "Net-(Q8-B)") (class "Default")
      (node (ref "Q8") (pin "1") (pinfunction "B_1") (pintype "passive"))
      (node (ref "R211") (pin "2") (pinfunction "2_2") (pintype "passive"))
    )
    (net (code "70") (name "Net-(Q8-C)") (class "Default")
      (node (ref "Q8") (pin "3") (pinfunction "C_3") (pintype "passive"))
      (node (ref "R11") (pin "2") (pinfunction "2_2") (pintype "passive"))
    )
    (net (code "71") (name "Net-(Q9-B)") (class "Default")
      (node (ref "Q9") (pin "1") (pinfunction "B_1") (pintype "passive"))
      (node (ref "R212") (pin "2") (pinfunction "2_2") (pintype "passive"))
    )
    (net (code "72") (name "Net-(Q9-C)") (class "Default")
      (node (ref "Q9") (pin "3") (pinfunction "C_3") (pintype "passive"))
      (node (ref "R9") (pin "2") (pinfunction "2_2") (pintype "passive"))
    )
    (net (code "73") (name "Net-(Q10-B)") (class "Default")
      (node (ref "Q10") (pin "1") (pinfunction "B_1") (pintype "passive"))
      (node (ref "R213") (pin "2") (pinfunction "2_2") (pintype "passive"))
    )
    (net (code "74") (name "Net-(Q10-C)") (class "Default")
      (node (ref "Q10") (pin "3") (pinfunction "C_3") (pintype "passive"))
      (node (ref "R7") (pin "2") (pinfunction "2_2") (pintype "passive"))
    )
    (net (code "75") (name "Net-(Q11-B)") (class "Default")
      (node (ref "Q11") (pin "1") (pinfunction "B_1") (pintype "passive"))
      (node (ref "R214") (pin "2") (pinfunction "2_2") (pintype "passive"))
    )
    (net (code "76") (name "Net-(Q11-C)") (class "Default")
      (node (ref "Q11") (pin "3") (pinfunction "C_3") (pintype "passive"))
      (node (ref "R5") (pin "2") (pinfunction "2_2") (pintype "passive"))
    )
    (net (code "77") (name "Net-(TC1-OUT)") (class "Default")
      (node (ref "R207") (pin "2") (pinfunction "2_2") (pintype "passive"))
      (node (ref "TC1") (pin "1") (pinfunction "OUT_1") (pintype "bidirectional"))
    )
    (net (code "78") (name "Net-(U2-V_OUT)") (class "Default")
      (node (ref "R206") (pin "2") (pinfunction "2_2") (pintype "passive"))
      (node (ref "U2") (pin "5") (pinfunction "V_OUT_5") (pintype "bidirectional"))
    )
    (net (code "79") (name "Net-(U3-X_OUT)") (class "Default")
      (node (ref "R208") (pin "2") (pinfunction "2_2") (pintype "passive"))
      (node (ref "U3") (pin "12") (pinfunction "X_OUT_12") (pintype "bidirectional"))
    )
    (net (code "80") (name "Net-(U3-Y_OUT)") (class "Default")
      (node (ref "R209") (pin "2") (pinfunction "2_2") (pintype "passive"))
      (node (ref "U3") (pin "10") (pinfunction "Y_OUT_10") (pintype "bidirectional"))
    )
    (net (code "81") (name "Net-(U3-Z_OUT)") (class "Default")
      (node (ref "R210") (pin "2") (pinfunction "2_2") (pintype "passive"))
      (node (ref "U3") (pin "8") (pinfunction "Z_OUT_8") (pintype "bidirectional"))
    )
    (net (code "82") (name "OPT2_IN") (class "Default")
      (node (ref "J11") (pin "3") (pinfunction "3_3") (pintype "passive"))
      (node (ref "U1") (pin "6") (pinfunction "6/PWM_6") (pintype "bidirectional"))
    )
    (net (code "83") (name "OPT3_IN") (class "Default")
      (node (ref "J12") (pin "3") (pinfunction "3_3") (pintype "passive"))
      (node (ref "U1") (pin "7") (pinfunction "7/RX3_7") (pintype "bidirectional"))
    )
    (net (code "84") (name "OPT4_IN") (class "Default")
      (node (ref "J13") (pin "3") (pinfunction "3_3") (pintype "passive"))
      (node (ref "U1") (pin "8") (pinfunction "8/TX3_8") (pintype "bidirectional"))
    )
    (net (code "85") (name "RLED_EN") (class "Default")
      (node (ref "R15") (pin "1") (pinfunction "1_1") (pintype "passive"))
      (node (ref "R80") (pin "1") (pinfunction "1_1") (pintype "passive"))
      (node (ref "U1") (pin "30") (pinfunction "30/A19/SDA1_30") (pintype "bidirectional"))
    )
    (net (code "86") (name "ROT_IN") (class "Default")
      (node (ref "J6") (pin "3") (pinfunction "3_3") (pintype "passive"))
      (node (ref "U1") (pin "4") (pinfunction "4/CAN-RX-PWM_4") (pintype "bidirectional"))
    )
    (net (code "87") (name "RPM_IN") (class "Default")
      (node (ref "J5") (pin "3") (pinfunction "3_3") (pintype "passive"))
      (node (ref "U1") (pin "2") (pinfunction "2_2") (pintype "bidirectional"))
    )
    (net (code "88") (name "TC_OUT") (class "Default")
      (node (ref "C105") (pin "1") (pinfunction "1_1") (pintype "passive"))
      (node (ref "R207") (pin "1") (pinfunction "1_1") (pintype "passive"))
      (node (ref "R302") (pin "1") (pinfunction "1_1") (pintype "passive"))
      (node (ref "U1") (pin "23/A9") (pinfunction "23/A9/T/PWM_23/A9") (pintype "bidirectional"))
    )
    (net (code "89") (name "V_BATT") (class "Default")
      (node (ref "BATT+") (pin "P") (pinfunction "1_P") (pintype "passive"))
      (node (ref "C8") (pin "1") (pinfunction "1_1") (pintype "passive"))
      (node (ref "ESC_PWR") (pin "2") (pinfunction "2_2") (pintype "bidirectional"))
      (node (ref "J8") (pin "1") (pinfunction "1_1") (pintype "bidirectional"))
      (node (ref "R666") (pin "1") (pinfunction "1_1") (pintype "passive"))
      (node (ref "VR1") (pin "1") (pinfunction "IN_1") (pintype "input"))
    )
    (net (code "90") (name "V_BATT_SENSE_EN") (class "Default")
      (node (ref "R109") (pin "2") (pinfunction "2_2") (pintype "passive"))
      (node (ref "U1") (pin "13") (pinfunction "13/SCK/LED_13") (pintype "bidirectional"))
    )
    (net (code "91") (name "X_IN") (class "Default")
      (node (ref "J3") (pin "3") (pinfunction "3_3") (pintype "passive"))
      (node (ref "U1") (pin "0") (pinfunction "0/RX1/T_0") (pintype "bidirectional"))
    )
    (net (code "92") (name "Y_IN") (class "Default")
      (node (ref "J4") (pin "3") (pinfunction "3_3") (pintype "passive"))
      (node (ref "U1") (pin "1") (pinfunction "1/TX1/T_1") (pintype "bidirectional"))
    )
    (net (code "93") (name "unconnected-(U1-9{slash}RX2{slash}PWM-Pad9)") (class "Default")
      (node (ref "U1") (pin "9") (pinfunction "9/RX2/PWM_9") (pintype "bidirectional"))
    )
    (net (code "94") (name "unconnected-(U1-10{slash}TX2{slash}PWM-Pad10)") (class "Default")
      (node (ref "U1") (pin "10") (pinfunction "10/TX2/PWM_10") (pintype "bidirectional"))
    )
    (net (code "95") (name "unconnected-(U1-A14{slash}DAC-PadA14)") (class "Default")
      (node (ref "U1") (pin "A14") (pinfunction "A14/DAC_A14") (pintype "bidirectional"))
    )
    (net (code "96") (name "unconnected-(U1-Pad24)") (class "Default")
      (node (ref "U1") (pin "24") (pinfunction "24_24") (pintype "bidirectional"))
    )
    (net (code "97") (name "unconnected-(U1-PadA10)") (class "Default")
      (node (ref "U1") (pin "A10") (pinfunction "A10_A10") (pintype "bidirectional"))
    )
    (net (code "98") (name "unconnected-(U1-PadA11)") (class "Default")
      (node (ref "U1") (pin "A11") (pinfunction "A11_A11") (pintype "bidirectional"))
    )
    (net (code "99") (name "unconnected-(U1-PadA12)") (class "Default")
      (node (ref "U1") (pin "A12") (pinfunction "A12_A12") (pintype "bidirectional"))
    )
    (net (code "100") (name "unconnected-(U1-PadA13)") (class "Default")
      (node (ref "U1") (pin "A13") (pinfunction "A13_A13") (pintype "bidirectional"))
    )
    (net (code "101") (name "unconnected-(U1-PadPGM)") (class "Default")
      (node (ref "U1") (pin "PGM") (pinfunction "PGM_PGM") (pintype "bidirectional"))
    )
  )
)
